# USB_OTG_FS.net
KiCad netlist of a schematic drawn in Altium Designer
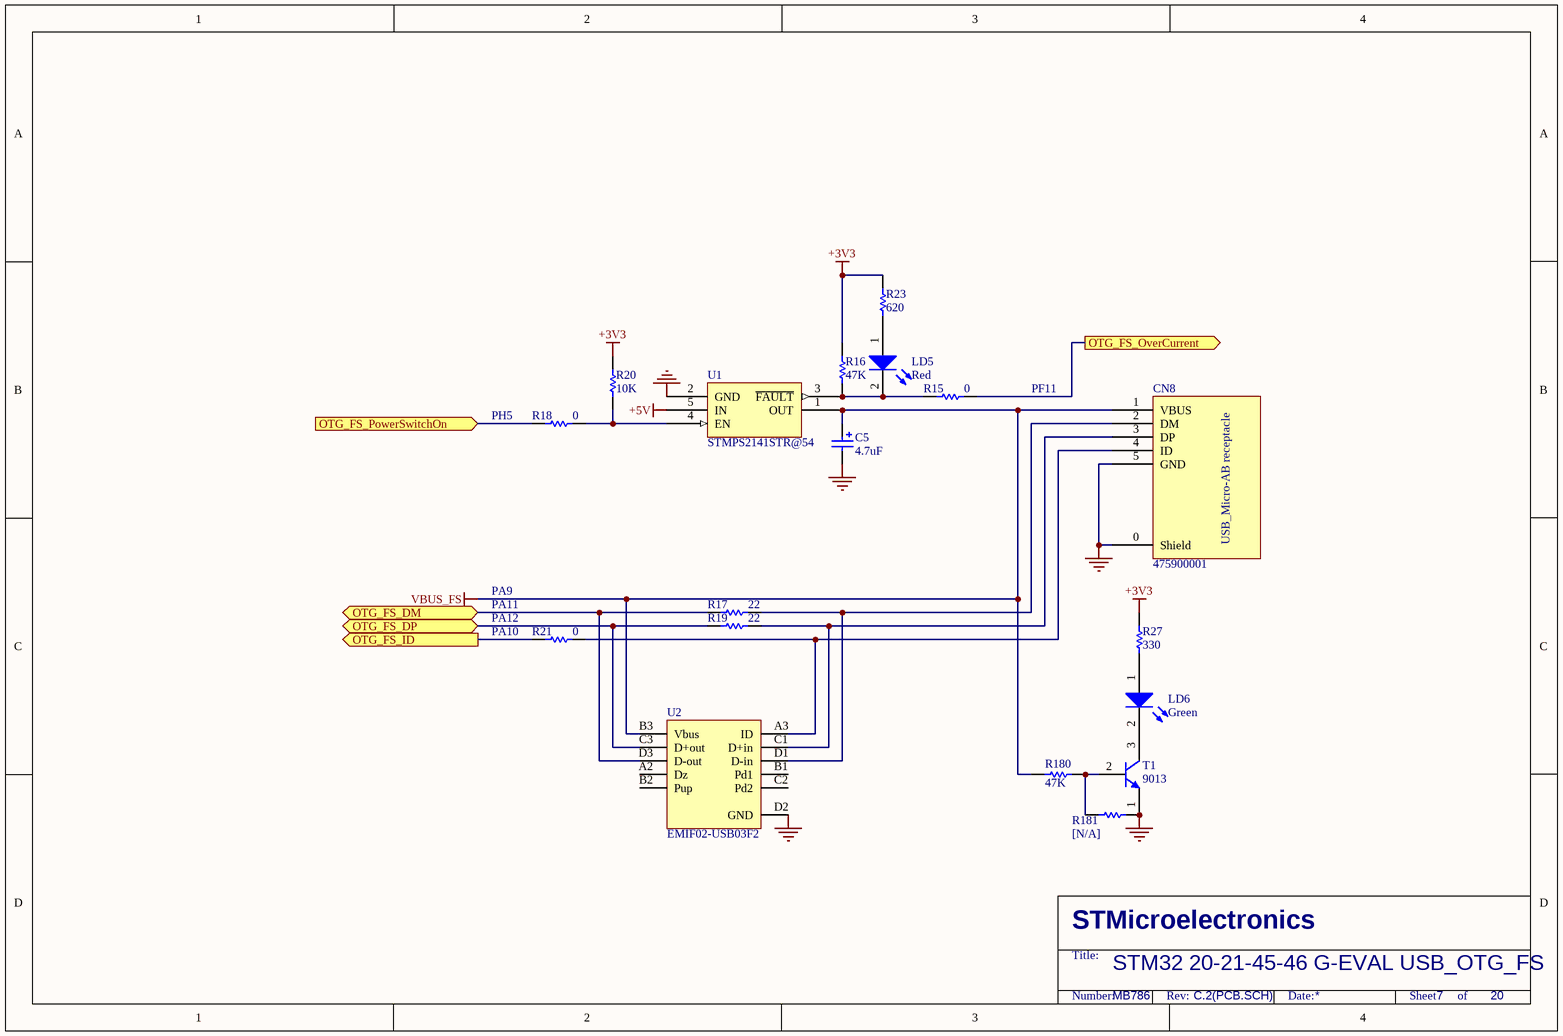
[diagram p0: USB_OTG_FS.SchDoc]

(export (version "E")
  (design (tool "Eeschema 10.0.6"))
  (components
    (comp (ref "C5")
      (value "4.7uF")
      (footprint "TAN-A")
      (description "Polarized Capacitor (Radial)")
      (fields (field (name "PUBLISHER") "Altium Limited"))
      (libsource (lib "Miscellaneous Devices") (part "Cap Pol1"))
    )
    (comp (ref "CN8")
      (value "475900001")
      (footprint "USB-MICRO-AB")
      (libsource (lib "MB786") (part "475900001"))
    )
    (comp (ref "LD5")
      (value "Red")
      (footprint "0603D")
      (description "Typical RED, GREEN, YELLOW, AMBER GaAs LED")
      (fields (field (name "PUBLISHER") "Altium Limited"))
      (libsource (lib "Miscellaneous Devices") (part "LED2"))
    )
    (comp (ref "LD6")
      (value "Green")
      (footprint "0603D")
      (description "Typical RED, GREEN, YELLOW, AMBER GaAs LED")
      (fields (field (name "PUBLISHER") "Altium Limited"))
      (libsource (lib "Miscellaneous Devices") (part "LED2"))
    )
    (comp (ref "R15")
      (value "0")
      (footprint "0603R")
      (description "Resistor")
      (fields (field (name "PUBLISHER") "Altium Limited"))
      (libsource (lib "Miscellaneous Devices") (part "Res1"))
    )
    (comp (ref "R16")
      (value "47K")
      (footprint "0402R")
      (description "Resistor")
      (fields (field (name "PUBLISHER") "Altium Limited"))
      (libsource (lib "Miscellaneous Devices") (part "res1"))
    )
    (comp (ref "R17")
      (value "22")
      (footprint "0603R")
      (description "Resistor")
      (fields (field (name "PUBLISHER") "Altium Limited"))
      (libsource (lib "Miscellaneous Devices") (part "Res1"))
    )
    (comp (ref "R18")
      (value "0")
      (footprint "0603R")
      (description "Resistor")
      (fields (field (name "PUBLISHER") "Altium Limited"))
      (libsource (lib "Miscellaneous Devices") (part "Res1"))
    )
    (comp (ref "R19")
      (value "22")
      (footprint "0603R")
      (description "Resistor")
      (fields (field (name "PUBLISHER") "Altium Limited"))
      (libsource (lib "Miscellaneous Devices") (part "Res1"))
    )
    (comp (ref "R20")
      (value "10K")
      (footprint "0402R")
      (description "Resistor")
      (fields (field (name "PUBLISHER") "Altium Limited"))
      (libsource (lib "Miscellaneous Devices") (part "res1"))
    )
    (comp (ref "R21")
      (value "0")
      (footprint "0603R")
      (description "Resistor")
      (fields (field (name "PUBLISHER") "Altium Limited"))
      (libsource (lib "Miscellaneous Devices") (part "Res1"))
    )
    (comp (ref "R23")
      (value "620")
      (footprint "0603R")
      (description "Resistor")
      (fields (field (name "PUBLISHER") "Altium Limited"))
      (libsource (lib "Miscellaneous Devices") (part "Res1"))
    )
    (comp (ref "R27")
      (value "330")
      (footprint "0603R")
      (description "Resistor")
      (fields (field (name "PUBLISHER") "Altium Limited"))
      (libsource (lib "Miscellaneous Devices") (part "res1"))
    )
    (comp (ref "R180")
      (value "47K")
      (footprint "0402R")
      (description "Resistor")
      (fields (field (name "PUBLISHER") "Altium Limited"))
      (libsource (lib "Miscellaneous Devices") (part "res1"))
    )
    (comp (ref "R181")
      (value "[N/A]")
      (footprint "0603R")
      (description "Resistor")
      (fields (field (name "PUBLISHER") "Altium Limited"))
      (libsource (lib "Miscellaneous Devices") (part "res1"))
    )
    (comp (ref "T1")
      (value "9013")
      (footprint "SOT-23")
      (description "NPN Bipolar Transistor")
      (fields (field (name "PUBLISHER") "Altium Limited"))
      (libsource (lib "Miscellaneous Devices") (part "NPN"))
    )
    (comp (ref "U1")
      (value "STMPS2141STR@54")
      (footprint "SOT-23-5L")
      (libsource (lib "MB784") (part "STMPS2141STR"))
    )
    (comp (ref "U2")
      (value "EMIF02-USB03F2")
      (footprint "FlipChip(11)")
      (libsource (lib "MB784") (part "EMIF02-USB03F2"))
    )
  )
  (nets
    (net (code "1") (name "+3V3") (class "Default")
      (node (ref "R16") (pin "1") (pinfunction "1_1") (pintype "passive"))
      (node (ref "R20") (pin "1") (pinfunction "1_1") (pintype "passive"))
      (node (ref "R23") (pin "2") (pinfunction "2_2") (pintype "passive"))
      (node (ref "R27") (pin "2") (pinfunction "2_2") (pintype "passive"))
    )
    (net (code "2") (name "+5V") (class "Default")
      (node (ref "U1") (pin "5") (pinfunction "IN_5") (pintype "passive"))
    )
    (net (code "3") (name "/OTG_FS_DM") (class "Default")
      (node (ref "R17") (pin "2") (pinfunction "2_2") (pintype "passive"))
      (node (ref "U2") (pin "D3") (pinfunction "D-out_D3") (pintype "passive"))
    )
    (net (code "4") (name "/OTG_FS_DP") (class "Default")
      (node (ref "R19") (pin "2") (pinfunction "2_2") (pintype "passive"))
      (node (ref "U2") (pin "C3") (pinfunction "D+out_C3") (pintype "passive"))
    )
    (net (code "5") (name "/OTG_FS_ID") (class "Default")
      (node (ref "R21") (pin "2") (pinfunction "2_2") (pintype "passive"))
    )
    (net (code "6") (name "/OTG_FS_OverCurrent") (class "Default")
      (node (ref "R15") (pin "1") (pinfunction "1_1") (pintype "passive"))
    )
    (net (code "7") (name "/OTG_FS_PowerSwitchOn") (class "Default")
      (node (ref "R18") (pin "2") (pinfunction "2_2") (pintype "passive"))
    )
    (net (code "8") (name "GND") (class "Default")
      (node (ref "C5") (pin "2") (pinfunction "2_2") (pintype "passive"))
      (node (ref "CN8") (pin "0") (pinfunction "Shield_0") (pintype "passive"))
      (node (ref "CN8") (pin "5") (pinfunction "GND_5") (pintype "passive"))
      (node (ref "R181") (pin "1") (pinfunction "1_1") (pintype "passive"))
      (node (ref "T1") (pin "1") (pinfunction "E_1") (pintype "passive"))
      (node (ref "U1") (pin "2") (pinfunction "GND_2") (pintype "passive"))
      (node (ref "U2") (pin "D2") (pinfunction "GND_D2") (pintype "passive"))
    )
    (net (code "9") (name "Net-(CN8-DM)") (class "Default")
      (node (ref "CN8") (pin "2") (pinfunction "DM_2") (pintype "passive"))
      (node (ref "R17") (pin "1") (pinfunction "1_1") (pintype "passive"))
      (node (ref "U2") (pin "D1") (pinfunction "D-in_D1") (pintype "passive"))
    )
    (net (code "10") (name "Net-(CN8-DP)") (class "Default")
      (node (ref "CN8") (pin "3") (pinfunction "DP_3") (pintype "passive"))
      (node (ref "R19") (pin "1") (pinfunction "1_1") (pintype "passive"))
      (node (ref "U2") (pin "C1") (pinfunction "D+in_C1") (pintype "passive"))
    )
    (net (code "11") (name "Net-(CN8-ID)") (class "Default")
      (node (ref "CN8") (pin "4") (pinfunction "ID_4") (pintype "passive"))
      (node (ref "R21") (pin "1") (pinfunction "1_1") (pintype "passive"))
      (node (ref "U2") (pin "A3") (pinfunction "ID_A3") (pintype "passive"))
    )
    (net (code "12") (name "Net-(LD5-A)") (class "Default")
      (node (ref "LD5") (pin "1") (pinfunction "A_1") (pintype "passive"))
      (node (ref "R23") (pin "1") (pinfunction "1_1") (pintype "passive"))
    )
    (net (code "13") (name "Net-(LD5-K)") (class "Default")
      (node (ref "LD5") (pin "2") (pinfunction "K_2") (pintype "passive"))
      (node (ref "R15") (pin "2") (pinfunction "2_2") (pintype "passive"))
      (node (ref "R16") (pin "2") (pinfunction "2_2") (pintype "passive"))
      (node (ref "U1") (pin "3") (pinfunction "~{FAULT}_3") (pintype "output"))
    )
    (net (code "14") (name "Net-(LD6-A)") (class "Default")
      (node (ref "LD6") (pin "1") (pinfunction "A_1") (pintype "passive"))
      (node (ref "R27") (pin "1") (pinfunction "1_1") (pintype "passive"))
    )
    (net (code "15") (name "Net-(LD6-K)") (class "Default")
      (node (ref "LD6") (pin "2") (pinfunction "K_2") (pintype "passive"))
      (node (ref "T1") (pin "3") (pinfunction "C_3") (pintype "passive"))
    )
    (net (code "16") (name "Net-(T1-B)") (class "Default")
      (node (ref "R180") (pin "1") (pinfunction "1_1") (pintype "passive"))
      (node (ref "R181") (pin "2") (pinfunction "2_2") (pintype "passive"))
      (node (ref "T1") (pin "2") (pinfunction "B_2") (pintype "passive"))
    )
    (net (code "17") (name "Net-(U1-EN)") (class "Default")
      (node (ref "R18") (pin "1") (pinfunction "1_1") (pintype "passive"))
      (node (ref "R20") (pin "2") (pinfunction "2_2") (pintype "passive"))
      (node (ref "U1") (pin "4") (pinfunction "EN_4") (pintype "input"))
    )
    (net (code "18") (name "VBUS_FS") (class "Default")
      (node (ref "C5") (pin "1") (pinfunction "1_1") (pintype "passive"))
      (node (ref "CN8") (pin "1") (pinfunction "VBUS_1") (pintype "passive"))
      (node (ref "R180") (pin "2") (pinfunction "2_2") (pintype "passive"))
      (node (ref "U1") (pin "1") (pinfunction "OUT_1") (pintype "passive"))
      (node (ref "U2") (pin "B3") (pinfunction "Vbus_B3") (pintype "passive"))
    )
    (net (code "19") (name "unconnected-(U2-Dz-PadA2)") (class "Default")
      (node (ref "U2") (pin "A2") (pinfunction "Dz_A2") (pintype "passive"))
    )
    (net (code "20") (name "unconnected-(U2-Pd1-PadB1)") (class "Default")
      (node (ref "U2") (pin "B1") (pinfunction "Pd1_B1") (pintype "passive"))
    )
    (net (code "21") (name "unconnected-(U2-Pd2-PadC2)") (class "Default")
      (node (ref "U2") (pin "C2") (pinfunction "Pd2_C2") (pintype "passive"))
    )
    (net (code "22") (name "unconnected-(U2-Pup-PadB2)") (class "Default")
      (node (ref "U2") (pin "B2") (pinfunction "Pup_B2") (pintype "passive"))
    )
  )
)
